# LPEDT_revA1_bikeit_DEBUG_MECH.net
KiCad netlist of a schematic drawn in Altium Designer
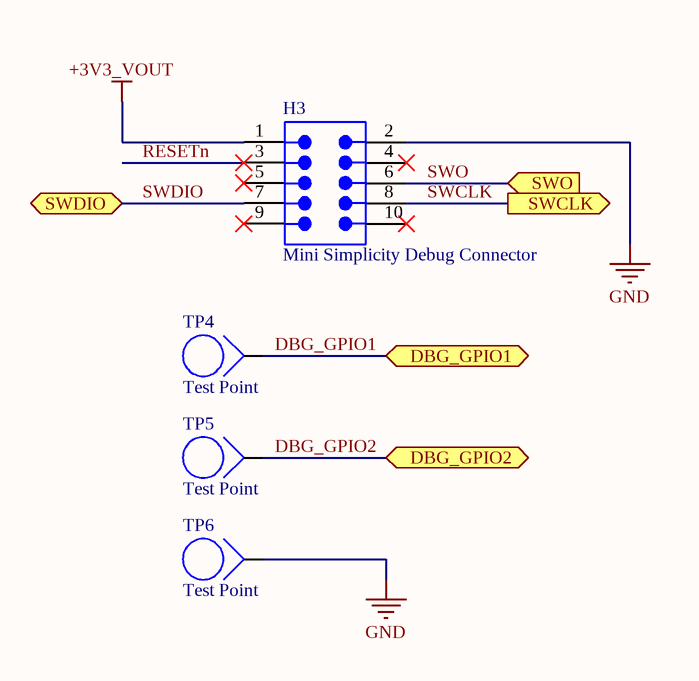
[diagram p0: LPEDT_revA1_bikeit_DEBUG_MECH.SchDoc]

(export (version "E")
  (design (tool "Eeschema 10.0.6"))
  (components
    (comp (ref "H3")
      (value "Mini Simplicity Debug Connector")
      (description "Conn Unshrouded Header HDR 10 POS 1.27mm Solder ST SMD Tube")
      (fields
        (field (name "MANUFACTURER") "Samtec")
        (field (name "MANUFACTURER PART NUMBER") "FTSH-105-01-LM-DV-K")
      )
      (libsource (lib "LPEDT_revA1_bikeit_IL") (part "FTSH-105-01-LM-DV-K"))
    )
    (comp (ref "TP4") (value "Test Point") (libsource (lib "LPEDT_revA1_bikeit_IL") (part "Test Pad")))
    (comp (ref "TP5") (value "Test Point") (libsource (lib "LPEDT_revA1_bikeit_IL") (part "Test Pad")))
    (comp (ref "TP6") (value "Test Point") (libsource (lib "LPEDT_revA1_bikeit_IL") (part "Test Pad")))
  )
  (nets
    (net (code "1") (name "+3V3_VOUT") (class "Default")
      (node (ref "H3") (pin "1") (pinfunction "1_1") (pintype "passive"))
    )
    (net (code "2") (name "/DBG_GPIO1") (class "Default")
      (node (ref "TP4") (pin "1") (pinfunction "1_1") (pintype "passive"))
    )
    (net (code "3") (name "/DBG_GPIO2") (class "Default")
      (node (ref "TP5") (pin "1") (pinfunction "1_1") (pintype "passive"))
    )
    (net (code "4") (name "/RESETn") (class "Default")
      (node (ref "H3") (pin "3") (pinfunction "3_3") (pintype "passive+no_connect"))
    )
    (net (code "5") (name "/SWCLK") (class "Default")
      (node (ref "H3") (pin "8") (pinfunction "8_8") (pintype "passive"))
    )
    (net (code "6") (name "/SWDIO") (class "Default")
      (node (ref "H3") (pin "7") (pinfunction "7_7") (pintype "passive"))
    )
    (net (code "7") (name "/SWO") (class "Default")
      (node (ref "H3") (pin "6") (pinfunction "6_6") (pintype "passive"))
    )
    (net (code "8") (name "GND") (class "Default")
      (node (ref "H3") (pin "2") (pinfunction "2_2") (pintype "passive"))
      (node (ref "TP6") (pin "1") (pinfunction "1_1") (pintype "passive"))
    )
    (net (code "9") (name "unconnected-(H3-Pad4)") (class "Default")
      (node (ref "H3") (pin "4") (pinfunction "4_4") (pintype "passive+no_connect"))
    )
    (net (code "10") (name "unconnected-(H3-Pad5)") (class "Default")
      (node (ref "H3") (pin "5") (pinfunction "5_5") (pintype "passive+no_connect"))
    )
    (net (code "11") (name "unconnected-(H3-Pad9)") (class "Default")
      (node (ref "H3") (pin "9") (pinfunction "9_9") (pintype "passive+no_connect"))
    )
    (net (code "12") (name "unconnected-(H3-Pad10)") (class "Default")
      (node (ref "H3") (pin "10") (pinfunction "10_10") (pintype "passive+no_connect"))
    )
  )
)
